# badge-inner2-revA.net
KiCad netlist of a schematic drawn in EAGLE
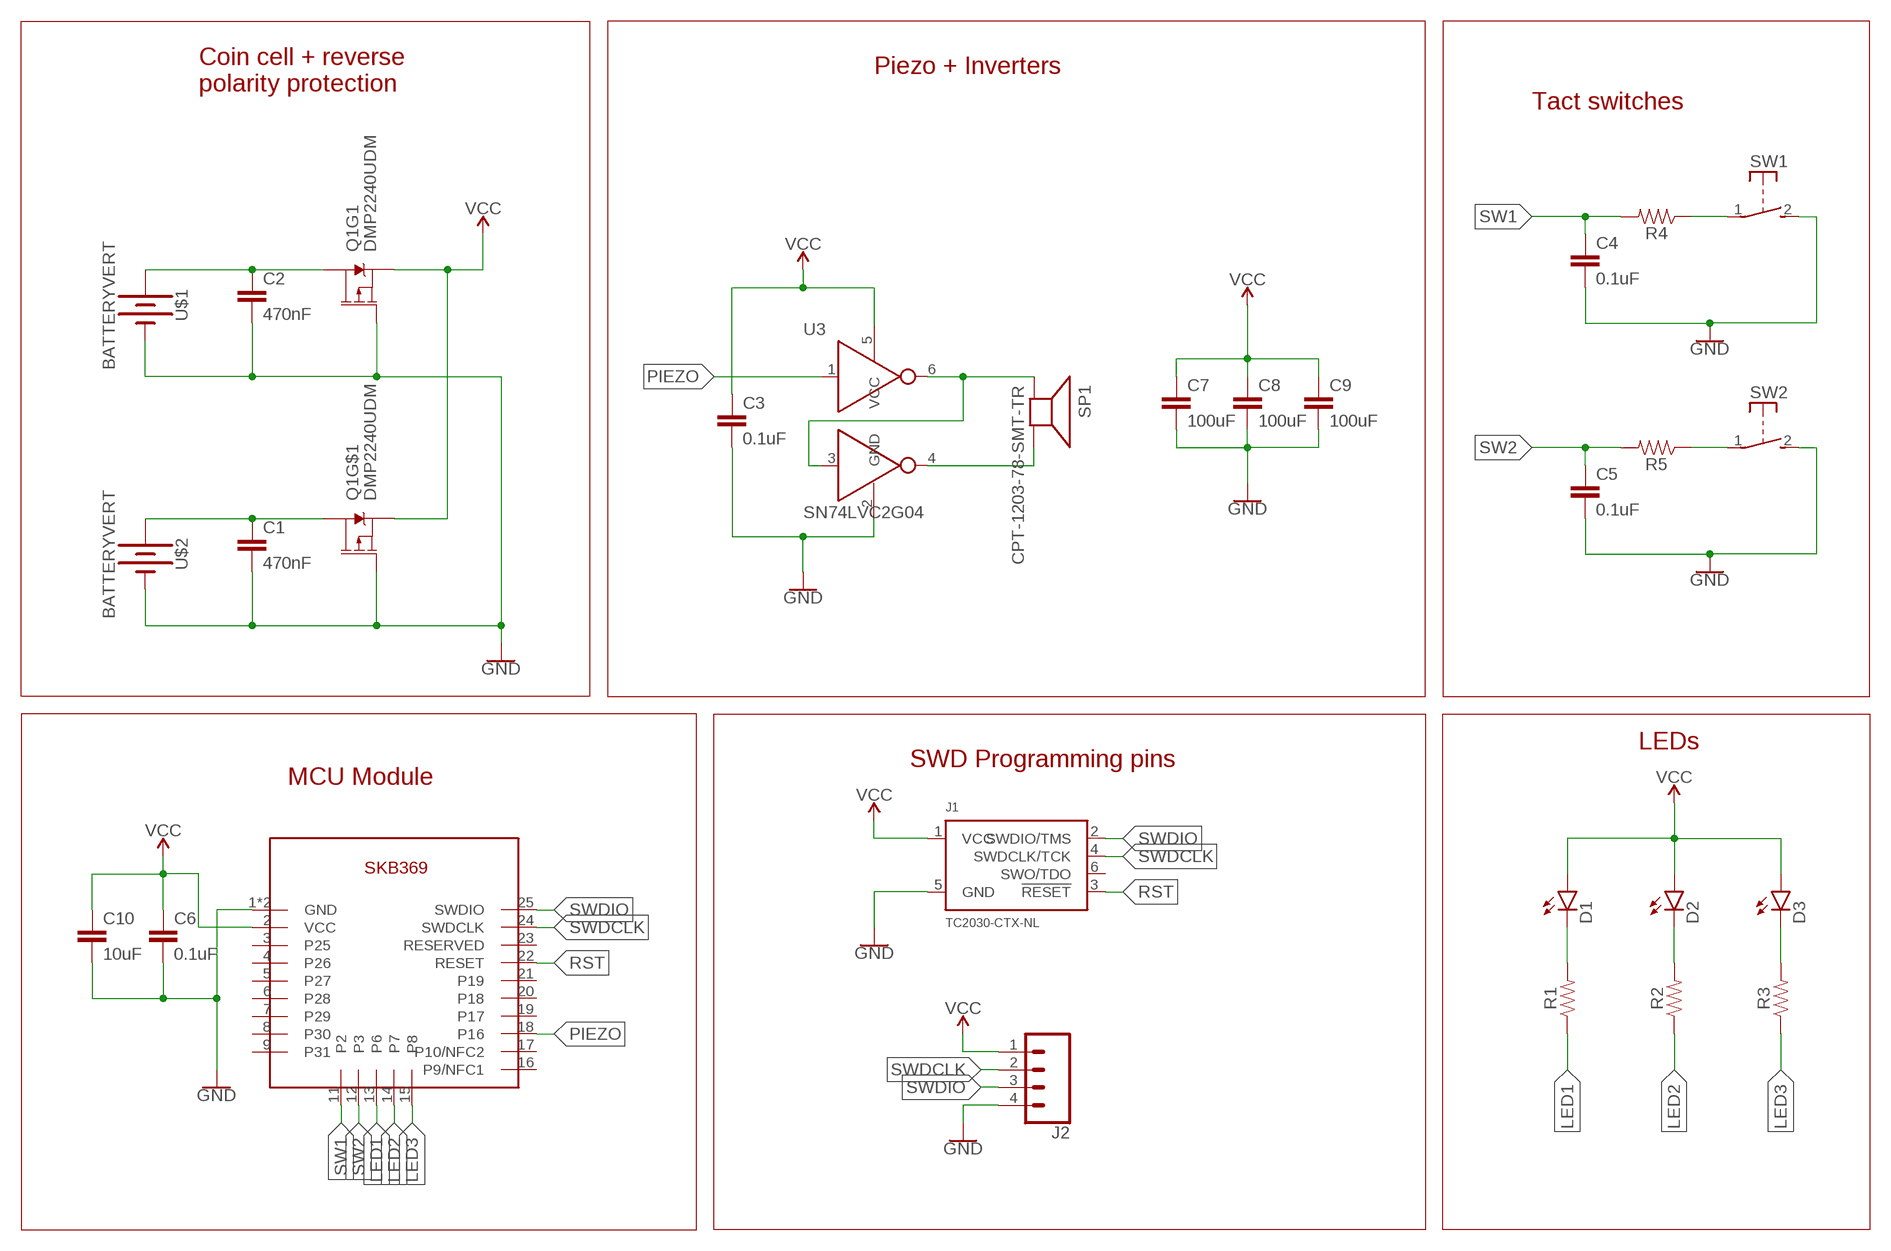
[diagram p0: schematic, sheet 1]

(export (version "E")
  (design (tool "Eeschema 10.0.6"))
  (components
    (comp (ref "C1")
      (value "470nF")
      (footprint "eagle-import:0603")
      (libsource (lib "eagle-import") (part "0.1UF-0603-25V-5%"))
    )
    (comp (ref "C2")
      (value "470nF")
      (footprint "eagle-import:0603")
      (libsource (lib "eagle-import") (part "0.1UF-0603-25V-5%"))
    )
    (comp (ref "C3")
      (value "0.1uF")
      (footprint "eagle-import:0603")
      (libsource (lib "eagle-import") (part "0.1UF-0603-25V-5%"))
    )
    (comp (ref "C4")
      (value "0.1uF")
      (footprint "eagle-import:0603")
      (libsource (lib "eagle-import") (part "0.1UF-0603-25V-5%"))
    )
    (comp (ref "C5")
      (value "0.1uF")
      (footprint "eagle-import:0603")
      (libsource (lib "eagle-import") (part "0.1UF-0603-25V-5%"))
    )
    (comp (ref "C6")
      (value "0.1uF")
      (footprint "eagle-import:0603")
      (libsource (lib "eagle-import") (part "0.1UF-0603-25V-5%"))
    )
    (comp (ref "C7")
      (value "100uF")
      (footprint "eagle-import:1206")
      (fields (field (name "SPICEPREFIX") "C"))
      (libsource (lib "eagle-import") (part "10UF-1206-6.3V-20%"))
    )
    (comp (ref "C8")
      (value "100uF")
      (footprint "eagle-import:1206")
      (fields (field (name "SPICEPREFIX") "C"))
      (libsource (lib "eagle-import") (part "10UF-1206-6.3V-20%"))
    )
    (comp (ref "C9")
      (value "100uF")
      (footprint "eagle-import:1206")
      (fields (field (name "SPICEPREFIX") "C"))
      (libsource (lib "eagle-import") (part "10UF-1206-6.3V-20%"))
    )
    (comp (ref "C10")
      (value "10uF")
      (footprint "eagle-import:0603")
      (libsource (lib "eagle-import") (part "0.1UF-0603-25V-5%"))
    )
    (comp (ref "D1")
      (value "SIDE-LED")
      (footprint "eagle-import:SIDE-LED")
      (libsource (lib "eagle-import") (part "SIDE-LED"))
    )
    (comp (ref "D2")
      (value "SIDE-LED")
      (footprint "eagle-import:SIDE-LED")
      (libsource (lib "eagle-import") (part "SIDE-LED"))
    )
    (comp (ref "D3")
      (value "SIDE-LED")
      (footprint "eagle-import:SIDE-LED")
      (libsource (lib "eagle-import") (part "SIDE-LED"))
    )
    (comp (ref "J1")
      (value "TC2030-CTX-NL")
      (footprint "eagle-import:TC2030-IDC-NL")
      (fields (field (name "MF") "Tag-Connect LLC") (field (name "MP") "TC2030-CTX"))
      (libsource (lib "eagle-import") (part "TC2030-CTX-NL"))
    )
    (comp (ref "J2")
      (value "CONN_04SMD_RA_FEMALE")
      (footprint "eagle-import:1X04_SMD_RA_FEMALE")
      (libsource (lib "eagle-import") (part "CONN_04SMD_RA_FEMALE"))
    )
    (comp (ref "Q1")
      (value "DMP2240UDM")
      (footprint "eagle-import:SOT26")
      (libsource (lib "eagle-import") (part "MOSFET_PCH_DUAL-DMP2240UDM"))
    )
    (comp (ref "R1")
      (value "0.05OHM-0603-1/5W-1%")
      (footprint "eagle-import:0603")
      (libsource (lib "eagle-import") (part "0.05OHM-0603-1/5W-1%"))
    )
    (comp (ref "R2")
      (value "0.05OHM-0603-1/5W-1%")
      (footprint "eagle-import:0603")
      (libsource (lib "eagle-import") (part "0.05OHM-0603-1/5W-1%"))
    )
    (comp (ref "R3")
      (value "0.05OHM-0603-1/5W-1%")
      (footprint "eagle-import:0603")
      (libsource (lib "eagle-import") (part "0.05OHM-0603-1/5W-1%"))
    )
    (comp (ref "R4")
      (value "0.05OHM-0603-1/5W-1%")
      (footprint "eagle-import:0603")
      (libsource (lib "eagle-import") (part "0.05OHM-0603-1/5W-1%"))
    )
    (comp (ref "R5")
      (value "0.05OHM-0603-1/5W-1%")
      (footprint "eagle-import:0603")
      (libsource (lib "eagle-import") (part "0.05OHM-0603-1/5W-1%"))
    )
    (comp (ref "SP1")
      (value "CPT-1203-78-SMT-TR")
      (footprint "eagle-import:CPT-1203-78-SMT-TR")
      (libsource (lib "eagle-import") (part "SPEAKER"))
    )
    (comp (ref "SW1")
      (value "EVQP4")
      (footprint "eagle-import:EVQP4KB")
      (libsource (lib "eagle-import") (part "EVQP4"))
    )
    (comp (ref "SW2")
      (value "EVQP4")
      (footprint "eagle-import:EVQP4KB")
      (libsource (lib "eagle-import") (part "EVQP4"))
    )
    (comp (ref "U$1")
      (value "BATTERYVERT")
      (footprint "eagle-import:VERTICAL-2032-PTH")
      (libsource (lib "eagle-import") (part "BATTERYVERT"))
    )
    (comp (ref "U$2")
      (value "BATTERYVERT")
      (footprint "eagle-import:VERTICAL-2032-PTH")
      (libsource (lib "eagle-import") (part "BATTERYVERT"))
    )
    (comp (ref "U1")
      (value "SKB369")
      (footprint "eagle-import:SKB369")
      (libsource (lib "eagle-import") (part "SKB369"))
    )
    (comp (ref "U3")
      (value "SN74LVC2G04")
      (footprint "eagle-import:SC70")
      (libsource (lib "eagle-import") (part "DUAL-INVERTERSN74LVC2G04"))
    )
  )
  (nets
    (net (code "1") (name "GND") (class "Default")
      (node (ref "C1") (pin "2") (pinfunction "2_2") (pintype "passive"))
      (node (ref "C10") (pin "2") (pinfunction "2_2") (pintype "passive"))
      (node (ref "C2") (pin "2") (pinfunction "2_2") (pintype "passive"))
      (node (ref "C3") (pin "2") (pinfunction "2_2") (pintype "passive"))
      (node (ref "C4") (pin "2") (pinfunction "2_2") (pintype "passive"))
      (node (ref "C5") (pin "2") (pinfunction "2_2") (pintype "passive"))
      (node (ref "C6") (pin "2") (pinfunction "2_2") (pintype "passive"))
      (node (ref "C7") (pin "2") (pinfunction "2_2") (pintype "passive"))
      (node (ref "C8") (pin "2") (pinfunction "2_2") (pintype "passive"))
      (node (ref "C9") (pin "2") (pinfunction "2_2") (pintype "passive"))
      (node (ref "J1") (pin "5") (pinfunction "GND_5") (pintype "bidirectional"))
      (node (ref "J2") (pin "4") (pinfunction "4_4") (pintype "passive"))
      (node (ref "Q1") (pin "G1") (pinfunction "G_G1") (pintype "bidirectional"))
      (node (ref "Q1") (pin "G2") (pinfunction "G_G2") (pintype "bidirectional"))
      (node (ref "SW1") (pin "2") (pinfunction "S_2") (pintype "passive"))
      (node (ref "SW2") (pin "2") (pinfunction "S_2") (pintype "passive"))
      (node (ref "U$1") (pin "-") (pinfunction "-_-") (pintype "power_in"))
      (node (ref "U$2") (pin "-") (pinfunction "-_-") (pintype "power_in"))
      (node (ref "U1") (pin "1") (pinfunction "GND_1") (pintype "bidirectional"))
      (node (ref "U1") (pin "10") (pinfunction "GND_10") (pintype "bidirectional"))
      (node (ref "U3") (pin "2") (pinfunction "GND_2") (pintype "bidirectional"))
    )
    (net (code "2") (name "LED1") (class "Default")
      (node (ref "R1") (pin "1") (pinfunction "1_1") (pintype "passive"))
      (node (ref "U1") (pin "13") (pinfunction "P6_13") (pintype "bidirectional"))
    )
    (net (code "3") (name "LED2") (class "Default")
      (node (ref "R2") (pin "1") (pinfunction "1_1") (pintype "passive"))
      (node (ref "U1") (pin "14") (pinfunction "P7_14") (pintype "bidirectional"))
    )
    (net (code "4") (name "LED3") (class "Default")
      (node (ref "R3") (pin "1") (pinfunction "1_1") (pintype "passive"))
      (node (ref "U1") (pin "15") (pinfunction "P8_15") (pintype "bidirectional"))
    )
    (net (code "5") (name "Net-(D1-C)") (class "Default")
      (node (ref "D1") (pin "1") (pinfunction "C_1") (pintype "passive"))
      (node (ref "R1") (pin "2") (pinfunction "2_2") (pintype "passive"))
    )
    (net (code "6") (name "Net-(D2-C)") (class "Default")
      (node (ref "D2") (pin "1") (pinfunction "C_1") (pintype "passive"))
      (node (ref "R2") (pin "2") (pinfunction "2_2") (pintype "passive"))
    )
    (net (code "7") (name "Net-(D3-C)") (class "Default")
      (node (ref "D3") (pin "1") (pinfunction "C_1") (pintype "passive"))
      (node (ref "R3") (pin "2") (pinfunction "2_2") (pintype "passive"))
    )
    (net (code "8") (name "Net-(Q1A-D)") (class "Default")
      (node (ref "C1") (pin "1") (pinfunction "1_1") (pintype "passive"))
      (node (ref "Q1") (pin "D2") (pinfunction "D_D2") (pintype "bidirectional"))
      (node (ref "U$2") (pin "P$4") (pinfunction "+_P$4") (pintype "power_in"))
      (node (ref "U$2") (pin "P$6") (pinfunction "+_P$6") (pintype "power_in"))
    )
    (net (code "9") (name "Net-(Q1B-D)") (class "Default")
      (node (ref "C2") (pin "1") (pinfunction "1_1") (pintype "passive"))
      (node (ref "Q1") (pin "D1") (pinfunction "D_D1") (pintype "bidirectional"))
      (node (ref "U$1") (pin "P$4") (pinfunction "+_P$4") (pintype "power_in"))
      (node (ref "U$1") (pin "P$6") (pinfunction "+_P$6") (pintype "power_in"))
    )
    (net (code "10") (name "Net-(SP1-+)") (class "Default")
      (node (ref "SP1") (pin "P$1") (pinfunction "+_P$1") (pintype "passive"))
      (node (ref "U3") (pin "3") (pinfunction "A2_3") (pintype "bidirectional"))
      (node (ref "U3") (pin "6") (pinfunction "Y1_6") (pintype "bidirectional"))
    )
    (net (code "11") (name "Net-(SP1--)") (class "Default")
      (node (ref "SP1") (pin "P$2") (pinfunction "-_P$2") (pintype "passive"))
      (node (ref "U3") (pin "4") (pinfunction "Y2_4") (pintype "bidirectional"))
    )
    (net (code "12") (name "Net-(SW1-P)") (class "Default")
      (node (ref "R4") (pin "1") (pinfunction "1_1") (pintype "passive"))
      (node (ref "SW1") (pin "1") (pinfunction "P_1") (pintype "passive"))
    )
    (net (code "13") (name "Net-(SW2-P)") (class "Default")
      (node (ref "R5") (pin "1") (pinfunction "1_1") (pintype "passive"))
      (node (ref "SW2") (pin "1") (pinfunction "P_1") (pintype "passive"))
    )
    (net (code "14") (name "PIEZO") (class "Default")
      (node (ref "U1") (pin "18") (pinfunction "P16_18") (pintype "bidirectional"))
      (node (ref "U3") (pin "1") (pinfunction "A1_1") (pintype "bidirectional"))
    )
    (net (code "15") (name "RST") (class "Default")
      (node (ref "J1") (pin "3") (pinfunction "~{RESET}_3") (pintype "bidirectional"))
      (node (ref "U1") (pin "22") (pinfunction "RESET_22") (pintype "bidirectional"))
    )
    (net (code "16") (name "SW1") (class "Default")
      (node (ref "C4") (pin "1") (pinfunction "1_1") (pintype "passive"))
      (node (ref "R4") (pin "2") (pinfunction "2_2") (pintype "passive"))
      (node (ref "U1") (pin "11") (pinfunction "P2_11") (pintype "bidirectional"))
    )
    (net (code "17") (name "SW2") (class "Default")
      (node (ref "C5") (pin "1") (pinfunction "1_1") (pintype "passive"))
      (node (ref "R5") (pin "2") (pinfunction "2_2") (pintype "passive"))
      (node (ref "U1") (pin "12") (pinfunction "P3_12") (pintype "bidirectional"))
    )
    (net (code "18") (name "SWDCLK") (class "Default")
      (node (ref "J1") (pin "4") (pinfunction "SWDCLK/TCK_4") (pintype "bidirectional"))
      (node (ref "J2") (pin "2") (pinfunction "2_2") (pintype "passive"))
      (node (ref "U1") (pin "24") (pinfunction "SWDCLK_24") (pintype "bidirectional"))
    )
    (net (code "19") (name "SWDIO") (class "Default")
      (node (ref "J1") (pin "2") (pinfunction "SWDIO/TMS_2") (pintype "bidirectional"))
      (node (ref "J2") (pin "3") (pinfunction "3_3") (pintype "passive"))
      (node (ref "U1") (pin "25") (pinfunction "SWDIO_25") (pintype "bidirectional"))
    )
    (net (code "20") (name "VCC") (class "Default")
      (node (ref "C10") (pin "1") (pinfunction "1_1") (pintype "passive"))
      (node (ref "C3") (pin "1") (pinfunction "1_1") (pintype "passive"))
      (node (ref "C6") (pin "1") (pinfunction "1_1") (pintype "passive"))
      (node (ref "C7") (pin "1") (pinfunction "1_1") (pintype "passive"))
      (node (ref "C8") (pin "1") (pinfunction "1_1") (pintype "passive"))
      (node (ref "C9") (pin "1") (pinfunction "1_1") (pintype "passive"))
      (node (ref "D1") (pin "2") (pinfunction "A_2") (pintype "passive"))
      (node (ref "D2") (pin "2") (pinfunction "A_2") (pintype "passive"))
      (node (ref "D3") (pin "2") (pinfunction "A_2") (pintype "passive"))
      (node (ref "J1") (pin "1") (pinfunction "VCC_1") (pintype "bidirectional"))
      (node (ref "J2") (pin "1") (pinfunction "1_1") (pintype "passive"))
      (node (ref "Q1") (pin "S1") (pinfunction "S_S1") (pintype "bidirectional"))
      (node (ref "Q1") (pin "S2") (pinfunction "S_S2") (pintype "bidirectional"))
      (node (ref "U1") (pin "2") (pinfunction "VCC_2") (pintype "bidirectional"))
      (node (ref "U3") (pin "5") (pinfunction "VCC_5") (pintype "bidirectional"))
    )
    (net (code "21") (name "unconnected-(J1-SWO{slash}TDO-Pad6)") (class "Default")
      (node (ref "J1") (pin "6") (pinfunction "SWO/TDO_6") (pintype "bidirectional"))
    )
    (net (code "22") (name "unconnected-(U1-P9{slash}NFC1-Pad16)") (class "Default")
      (node (ref "U1") (pin "16") (pinfunction "P9/NFC1_16") (pintype "bidirectional"))
    )
    (net (code "23") (name "unconnected-(U1-P10{slash}NFC2-Pad17)") (class "Default")
      (node (ref "U1") (pin "17") (pinfunction "P10/NFC2_17") (pintype "bidirectional"))
    )
    (net (code "24") (name "unconnected-(U1-P17-Pad19)") (class "Default")
      (node (ref "U1") (pin "19") (pinfunction "P17_19") (pintype "bidirectional"))
    )
    (net (code "25") (name "unconnected-(U1-P18-Pad20)") (class "Default")
      (node (ref "U1") (pin "20") (pinfunction "P18_20") (pintype "bidirectional"))
    )
    (net (code "26") (name "unconnected-(U1-P19-Pad21)") (class "Default")
      (node (ref "U1") (pin "21") (pinfunction "P19_21") (pintype "bidirectional"))
    )
    (net (code "27") (name "unconnected-(U1-P25-Pad3)") (class "Default")
      (node (ref "U1") (pin "3") (pinfunction "P25_3") (pintype "bidirectional"))
    )
    (net (code "28") (name "unconnected-(U1-P26-Pad4)") (class "Default")
      (node (ref "U1") (pin "4") (pinfunction "P26_4") (pintype "bidirectional"))
    )
    (net (code "29") (name "unconnected-(U1-P27-Pad5)") (class "Default")
      (node (ref "U1") (pin "5") (pinfunction "P27_5") (pintype "bidirectional"))
    )
    (net (code "30") (name "unconnected-(U1-P28-Pad6)") (class "Default")
      (node (ref "U1") (pin "6") (pinfunction "P28_6") (pintype "bidirectional"))
    )
    (net (code "31") (name "unconnected-(U1-P29-Pad7)") (class "Default")
      (node (ref "U1") (pin "7") (pinfunction "P29_7") (pintype "bidirectional"))
    )
    (net (code "32") (name "unconnected-(U1-P30-Pad8)") (class "Default")
      (node (ref "U1") (pin "8") (pinfunction "P30_8") (pintype "bidirectional"))
    )
    (net (code "33") (name "unconnected-(U1-P31-Pad9)") (class "Default")
      (node (ref "U1") (pin "9") (pinfunction "P31_9") (pintype "bidirectional"))
    )
    (net (code "34") (name "unconnected-(U1-RESERVED-Pad23)") (class "Default")
      (node (ref "U1") (pin "23") (pinfunction "RESERVED_23") (pintype "bidirectional"))
    )
  )
)
